# CTR_MCU_Circuits.net
KiCad netlist of a schematic drawn in Altium Designer
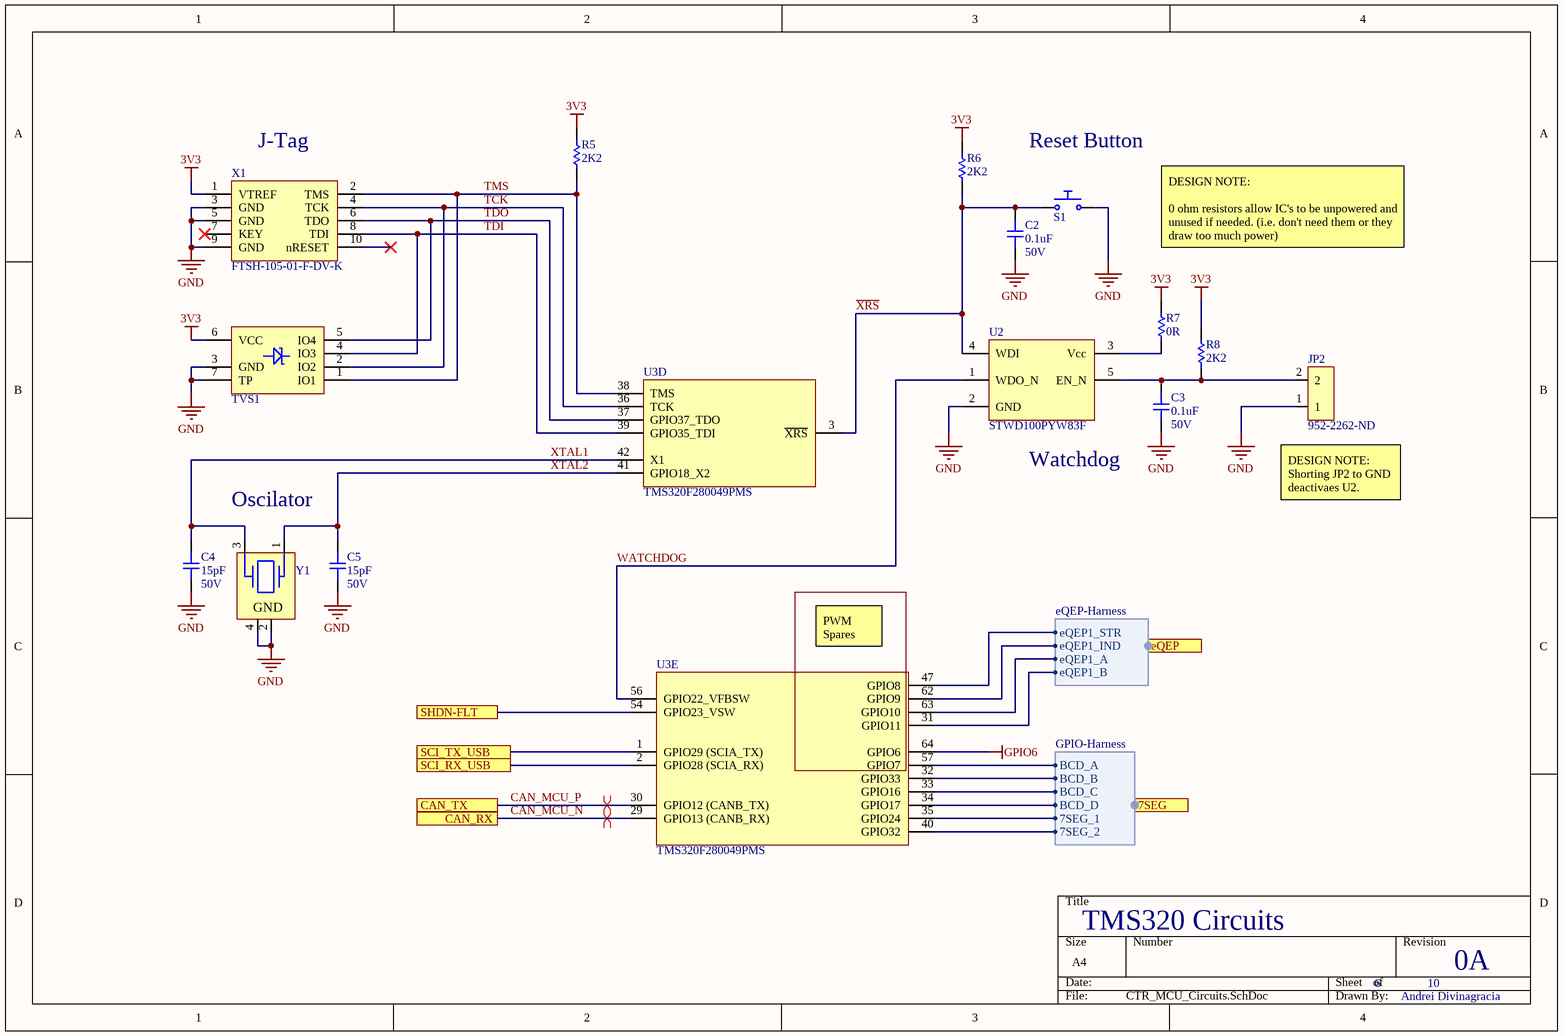
[diagram p0: CTR_MCU_Circuits.SchDoc]

(export (version "E")
  (design (tool "Eeschema 10.0.6"))
  (components
    (comp (ref "C2")
      (value "0.1uF")
      (footprint "CAP-0805")
      (description "CAP CER 0.1UF 50V Y5V 0805")
      (fields
        (field (name "MANUFACTURER") "KEMET")
        (field (name "MANUFACTURER PART NUMBER") "C0805C104Z5VACTU")
        (field (name "VOLTAGE RATING") "50V")
      )
      (libsource (lib "InverterSCHLib") (part "0805-0.1uF-50V"))
    )
    (comp (ref "C3")
      (value "0.1uF")
      (footprint "CAP-0805")
      (description "CAP CER 0.1UF 50V Y5V 0805")
      (fields
        (field (name "MANUFACTURER") "KEMET")
        (field (name "MANUFACTURER PART NUMBER") "C0805C104Z5VACTU")
        (field (name "VOLTAGE RATING") "50V")
      )
      (libsource (lib "InverterSCHLib") (part "0805-0.1uF-50V"))
    )
    (comp (ref "C4")
      (value "15pF")
      (footprint "CAP-0603")
      (description "CAP CER 15PF 50V C0G/NPO 0603")
      (fields
        (field (name "MANUFACTURER") "Yageo")
        (field (name "MANUFACTURER PART NUMBER") "CC0603JRNPO9BN150")
        (field (name "VOLTAGE RATING") "50V")
      )
      (libsource (lib "InverterSCHLib") (part "0603-15pF"))
    )
    (comp (ref "C5")
      (value "15pF")
      (footprint "CAP-0603")
      (description "CAP CER 15PF 50V C0G/NPO 0603")
      (fields
        (field (name "MANUFACTURER") "Yageo")
        (field (name "MANUFACTURER PART NUMBER") "CC0603JRNPO9BN150")
        (field (name "VOLTAGE RATING") "50V")
      )
      (libsource (lib "InverterSCHLib") (part "0603-15pF"))
    )
    (comp (ref "JP2")
      (value "952-2262-ND")
      (footprint "2PIN_HEADER")
      (description "CONN HEADER VERT 2POS 2.54MM")
      (fields (field (name "MANUFACTURER") "Harwin") (field (name "MANUFACTURER PART NUMBER") "M20-9990246"))
      (libsource (lib "InverterSCHLib") (part "M20-9990246"))
    )
    (comp (ref "R5")
      (value "2K2")
      (footprint "RES-0603")
      (description "RES SMD 2.2K OHM 5% 1/10W 0603")
      (fields
        (field (name "MANUFACTURER") "Yageo")
        (field (name "MANUFACTURER PART NUMBER") "AC0603JR-072K2L")
      )
      (libsource (lib "InverterSCHLib") (part "0603-2K2"))
    )
    (comp (ref "R6")
      (value "2K2")
      (footprint "RES-0603")
      (description "RES SMD 2.2K OHM 5% 1/10W 0603")
      (fields
        (field (name "MANUFACTURER") "Yageo")
        (field (name "MANUFACTURER PART NUMBER") "AC0603JR-072K2L")
      )
      (libsource (lib "InverterSCHLib") (part "0603-2K2"))
    )
    (comp (ref "R7")
      (value "0R")
      (footprint "RES-0603")
      (description "RES SMD 0 OHM JUMPER 1/10W 0603")
      (fields
        (field (name "MANUFACTURER") "Yageo")
        (field (name "MANUFACTURER PART NUMBER") "RC0603JR-070RL")
      )
      (libsource (lib "InverterSCHLib") (part "0603-0R"))
    )
    (comp (ref "R8")
      (value "2K2")
      (footprint "RES-0603")
      (description "RES SMD 2.2K OHM 5% 1/10W 0603")
      (fields
        (field (name "MANUFACTURER") "Yageo")
        (field (name "MANUFACTURER PART NUMBER") "AC0603JR-072K2L")
      )
      (libsource (lib "InverterSCHLib") (part "0603-2K2"))
    )
    (comp (ref "S1")
      (value "PTS645SM43SMTR92LFS")
      (footprint "PUSH_BUTTON")
      (description "SWITCH TACTILE SPST-NO 0.05A 12V")
      (fields (field (name "MANUFACTURER") "ITT C&K"))
      (libsource (lib "InverterSCHLib") (part "PTS645SM43SMTR92LFS"))
    )
    (comp (ref "TVS1")
      (value "TVS-4-5.5V-Bi")
      (footprint "TVS-DRS-TP-5")
      (description "TVS DIODE 5.5V 6SON")
      (fields
        (field (name "MANUFACTURER") "Texas Instruments")
        (field (name "MANUFACTURER PART NUMBER") "TPD4E001DRSR")
      )
      (libsource (lib "InverterSCHLib") (part "TVS-4-5.5V-Bi"))
    )
    (comp (ref "U2")
      (value "STWD100PYW83F")
      (footprint "SOT23-5-WATCHDOG")
      (description "IC WDT CIRCUIT SOT323-5")
      (fields (field (name "MANUFACTURER") "STMicroelectronics"))
      (libsource (lib "InverterSCHLib") (part "STWD100PYW83F"))
    )
    (comp (ref "U3")
      (value "TMS320F280049PMS")
      (footprint "64QFP")
      (description "IC MCU 32BIT 256KB FLASH 64LQFP")
      (fields
        (field (name "MANUFACTURER") "Texas Instruments")
        (field (name "MANUFACTURER PART NUMBER") "F280049CPMS")
      )
      (libsource (lib "InverterSCHLib") (part "TMS320F280049"))
    )
    (comp (ref "X1")
      (value "FTSH-105-01-F-DV-K")
      (footprint "JTAG_50mil_10pin")
      (description "CONN_JTAG_10pin .050 Connector Dual Header 10 Position Surface Mount")
      (fields (field (name "MANUFACTURER") "Samtec"))
      (libsource (lib "InverterSCHLib") (part "CONN-JTAG"))
    )
    (comp (ref "Y1")
      (value "ECS-200-18-30B-AGN-TR")
      (footprint "XTAL-SMD-4")
      (description "CRYSTAL 20.0000MHZ 18PF SMD")
      (fields (field (name "MANUFACTURER") "ECS International"))
      (libsource (lib "InverterSCHLib") (part "ECS-200-18-30B-AGN-TR"))
    )
  )
  (nets
    (net (code "3") (name "/7SEG_1") (class "Default")
      (node (ref "U3") (pin "35") (pinfunction "GPIO24_35") (pintype "passive"))
    )
    (net (code "4") (name "/7SEG_2") (class "Default")
      (node (ref "U3") (pin "40") (pinfunction "GPIO32_40") (pintype "passive"))
    )
    (net (code "5") (name "/BCD_A") (class "Default")
      (node (ref "U3") (pin "57") (pinfunction "GPIO7_57") (pintype "passive"))
    )
    (net (code "6") (name "/BCD_B") (class "Default")
      (node (ref "U3") (pin "32") (pinfunction "GPIO33_32") (pintype "passive"))
    )
    (net (code "7") (name "/BCD_C") (class "Default")
      (node (ref "U3") (pin "33") (pinfunction "GPIO16_33") (pintype "passive"))
    )
    (net (code "8") (name "/BCD_D") (class "Default")
      (node (ref "U3") (pin "34") (pinfunction "GPIO17_34") (pintype "passive"))
    )
    (net (code "9") (name "/CAN_MCU_N") (class "Default")
      (node (ref "U3") (pin "29") (pinfunction "GPIO13_(CANB_RX)_29") (pintype "passive"))
    )
    (net (code "10") (name "/CAN_MCU_P") (class "Default")
      (node (ref "U3") (pin "30") (pinfunction "GPIO12_(CANB_TX)_30") (pintype "passive"))
    )
    (net (code "11") (name "/SCI_RX_USB") (class "Default")
      (node (ref "U3") (pin "2") (pinfunction "GPIO28_(SCIA_RX)_2") (pintype "passive"))
    )
    (net (code "12") (name "/SCI_TX_USB") (class "Default")
      (node (ref "U3") (pin "1") (pinfunction "GPIO29_(SCIA_TX)_1") (pintype "passive"))
    )
    (net (code "13") (name "/SHDN-FLT") (class "Default")
      (node (ref "U3") (pin "54") (pinfunction "GPIO23_VSW_54") (pintype "passive"))
    )
    (net (code "14") (name "/TCK") (class "Default")
      (node (ref "TVS1") (pin "2") (pinfunction "IO2_2") (pintype "passive"))
      (node (ref "U3") (pin "36") (pinfunction "TCK_36") (pintype "passive"))
      (node (ref "X1") (pin "4") (pinfunction "TCK_4") (pintype "passive"))
    )
    (net (code "15") (name "/TDI") (class "Default")
      (node (ref "TVS1") (pin "4") (pinfunction "IO3_4") (pintype "passive"))
      (node (ref "U3") (pin "39") (pinfunction "GPIO35_TDI_39") (pintype "passive"))
      (node (ref "X1") (pin "8") (pinfunction "TDI_8") (pintype "passive"))
    )
    (net (code "16") (name "/TDO") (class "Default")
      (node (ref "TVS1") (pin "5") (pinfunction "IO4_5") (pintype "passive"))
      (node (ref "U3") (pin "37") (pinfunction "GPIO37_TDO_37") (pintype "passive"))
      (node (ref "X1") (pin "6") (pinfunction "TDO_6") (pintype "passive"))
    )
    (net (code "17") (name "/TMS") (class "Default")
      (node (ref "R5") (pin "2") (pinfunction "2_2") (pintype "passive"))
      (node (ref "TVS1") (pin "1") (pinfunction "IO1_1") (pintype "passive"))
      (node (ref "U3") (pin "38") (pinfunction "TMS_38") (pintype "passive"))
      (node (ref "X1") (pin "2") (pinfunction "TMS_2") (pintype "passive"))
    )
    (net (code "18") (name "/WATCHDOG") (class "Default")
      (node (ref "U2") (pin "1") (pinfunction "WDO_N_1") (pintype "passive"))
      (node (ref "U3") (pin "56") (pinfunction "GPIO22_VFBSW_56") (pintype "passive"))
    )
    (net (code "19") (name "/XTAL1") (class "Default")
      (node (ref "C4") (pin "2") (pinfunction "2_2") (pintype "passive"))
      (node (ref "U3") (pin "42") (pinfunction "X1_42") (pintype "passive"))
      (node (ref "Y1") (pin "3") (pinfunction "OUT_3") (pintype "passive"))
    )
    (net (code "20") (name "/XTAL2") (class "Default")
      (node (ref "C5") (pin "2") (pinfunction "2_2") (pintype "passive"))
      (node (ref "U3") (pin "41") (pinfunction "GPIO18_X2_41") (pintype "passive"))
      (node (ref "Y1") (pin "1") (pinfunction "IN_1") (pintype "passive"))
    )
    (net (code "21") (name "/eQEP1_A") (class "Default")
      (node (ref "U3") (pin "63") (pinfunction "GPIO10_63") (pintype "passive"))
    )
    (net (code "22") (name "/eQEP1_B") (class "Default")
      (node (ref "U3") (pin "31") (pinfunction "GPIO11_31") (pintype "passive"))
    )
    (net (code "23") (name "/eQEP1_IND") (class "Default")
      (node (ref "U3") (pin "62") (pinfunction "GPIO9_62") (pintype "passive"))
    )
    (net (code "24") (name "/eQEP1_STR") (class "Default")
      (node (ref "U3") (pin "47") (pinfunction "GPIO8_47") (pintype "passive"))
    )
    (net (code "27") (name "/~{XRS}") (class "Default")
      (node (ref "C2") (pin "2") (pinfunction "2_2") (pintype "passive"))
      (node (ref "R6") (pin "2") (pinfunction "2_2") (pintype "passive"))
      (node (ref "S1") (pin "1") (pinfunction "1_1") (pintype "passive"))
      (node (ref "U2") (pin "4") (pinfunction "WDI_4") (pintype "passive"))
      (node (ref "U3") (pin "3") (pinfunction "~{XRS}_3") (pintype "passive"))
    )
    (net (code "28") (name "3V3") (class "Default")
      (node (ref "R5") (pin "1") (pinfunction "1_1") (pintype "passive"))
      (node (ref "R6") (pin "1") (pinfunction "1_1") (pintype "passive"))
      (node (ref "R7") (pin "2") (pinfunction "2_2") (pintype "passive"))
      (node (ref "R8") (pin "2") (pinfunction "2_2") (pintype "passive"))
      (node (ref "TVS1") (pin "6") (pinfunction "VCC_6") (pintype "passive"))
      (node (ref "X1") (pin "1") (pinfunction "VTREF_1") (pintype "passive"))
    )
    (net (code "29") (name "GND") (class "Default")
      (node (ref "C2") (pin "1") (pinfunction "1_1") (pintype "passive"))
      (node (ref "C3") (pin "1") (pinfunction "1_1") (pintype "passive"))
      (node (ref "C4") (pin "1") (pinfunction "1_1") (pintype "passive"))
      (node (ref "C5") (pin "1") (pinfunction "1_1") (pintype "passive"))
      (node (ref "JP2") (pin "1") (pinfunction "1_1") (pintype "passive"))
      (node (ref "S1") (pin "2") (pinfunction "2_2") (pintype "passive"))
      (node (ref "TVS1") (pin "3") (pinfunction "GND_3") (pintype "passive"))
      (node (ref "TVS1") (pin "7") (pinfunction "TP_7") (pintype "passive"))
      (node (ref "U2") (pin "2") (pinfunction "GND_2") (pintype "passive"))
      (node (ref "X1") (pin "3") (pinfunction "GND_3") (pintype "passive"))
      (node (ref "X1") (pin "5") (pinfunction "GND_5") (pintype "passive"))
      (node (ref "X1") (pin "9") (pinfunction "GND_9") (pintype "passive"))
      (node (ref "Y1") (pin "2") (pinfunction "GND_2") (pintype "passive"))
      (node (ref "Y1") (pin "4") (pinfunction "GND_4") (pintype "passive"))
    )
    (net (code "30") (name "GPIO6") (class "Default")
      (node (ref "U3") (pin "64") (pinfunction "GPIO6_64") (pintype "passive"))
    )
    (net (code "31") (name "Net-(U2-EN_N)") (class "Default")
      (node (ref "C3") (pin "2") (pinfunction "2_2") (pintype "passive"))
      (node (ref "JP2") (pin "2") (pinfunction "2_2") (pintype "passive"))
      (node (ref "R8") (pin "1") (pinfunction "1_1") (pintype "passive"))
      (node (ref "U2") (pin "5") (pinfunction "EN_N_5") (pintype "passive"))
    )
    (net (code "32") (name "Net-(U2-Vcc)") (class "Default")
      (node (ref "R7") (pin "1") (pinfunction "1_1") (pintype "passive"))
      (node (ref "U2") (pin "3") (pinfunction "Vcc_3") (pintype "passive"))
    )
    (net (code "33") (name "unconnected-(X1-KEY-Pad7)") (class "Default")
      (node (ref "X1") (pin "7") (pinfunction "KEY_7") (pintype "passive+no_connect"))
    )
    (net (code "34") (name "unconnected-(X1-nRESET-Pad10)") (class "Default")
      (node (ref "X1") (pin "10") (pinfunction "nRESET_10") (pintype "passive+no_connect"))
    )
  )
)
